# st-link_v2_hall_crossboard_1_1.net
KiCad netlist of a schematic drawn in Altium Designer
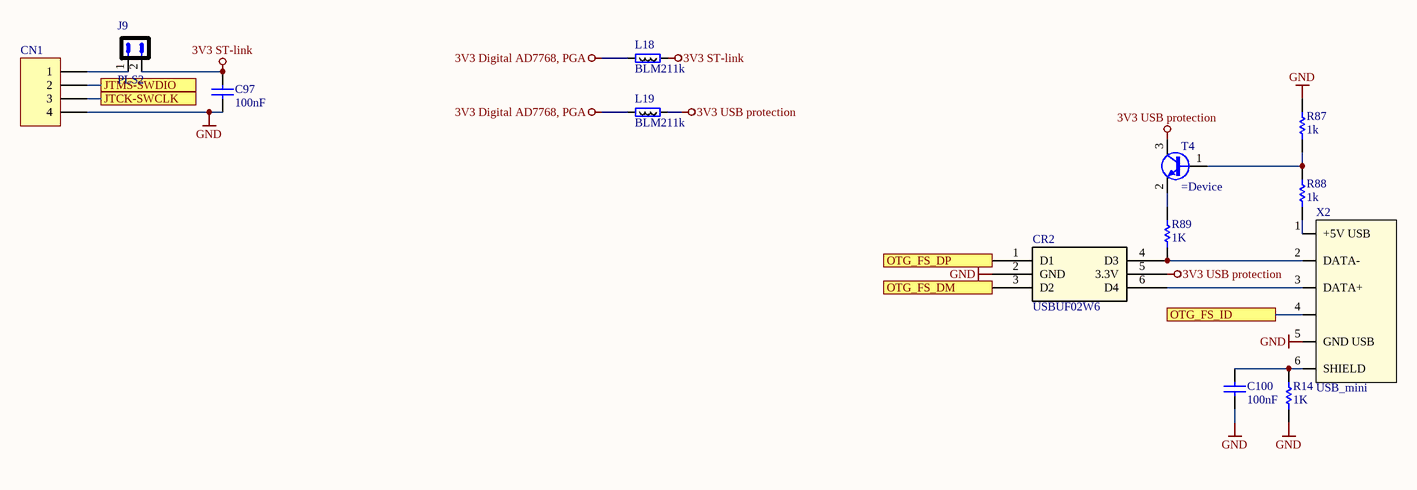
[diagram p0: st-link_v2_hall_crossboard_1_1.SchDoc]

(export (version "E")
  (design (tool "Eeschema 10.0.6"))
  (components
    (comp (ref "C97")
      (value "100nF")
      (footprint "hall_crossboard_1_1_library:0603C")
      (description "Capacitor 0402 / 0603 / 0805")
      (libsource (lib "hall_crossboard_1_1_library") (part "Capacitor_ST"))
    )
    (comp (ref "C100")
      (value "100nF")
      (footprint "hall_crossboard_1_1_library:0603C")
      (description "Capacitor 0402 / 0603 / 0805")
      (libsource (lib "hall_crossboard_1_1_library") (part "Capacitor_ST"))
    )
    (comp (ref "CN1")
      (value "Header 4")
      (footprint "HDR_1x4_2R54_V_M")
      (description "Header, 4-Pin, Single row")
      (fields (field (name "PUBLISHER") "Altium Limited"))
      (libsource (lib "schematic_hall_crossboard_1_1_library") (part "Header 4"))
    )
    (comp (ref "CR2")
      (value "USBUF02W6")
      (footprint "footprint_hall_crossboard_1_1_library:SOTT323-6L_STM-M")
      (description "USB protection")
      (libsource (lib "schematic_hall_crossboard_1_1_library") (part "USBUF02W6"))
    )
    (comp (ref "J9")
      (value "PLS2")
      (footprint "footprint_hall_crossboard_1_1_library:SAMTEC_TSW-102-23-L-S")
      (libsource (lib "schematic_hall_crossboard_1_1_library") (part "PLS2"))
    )
    (comp (ref "L18")
      (value "BLM211k")
      (footprint "footprint_hall_crossboard_1_1_library:RESC2012X50N")
      (description "SMD Ferrite bead 0805")
      (libsource (lib "schematic_hall_crossboard_1_1_library") (part "BLM21"))
    )
    (comp (ref "L19")
      (value "BLM211k")
      (footprint "footprint_hall_crossboard_1_1_library:RESC2012X50N")
      (description "SMD Ferrite bead 0805")
      (libsource (lib "schematic_hall_crossboard_1_1_library") (part "BLM21"))
    )
    (comp (ref "R14")
      (value "1K")
      (footprint "0603R")
      (description "Resistor 0402 / 0603 / 0805")
      (libsource (lib "hall_crossboard_1_1_library") (part "Resistor_ST"))
    )
    (comp (ref "R87")
      (value "1k")
      (footprint "0603R")
      (description "Resistor 0402 / 0603 / 0805")
      (libsource (lib "hall_crossboard_1_1_library") (part "Resistor_ST"))
    )
    (comp (ref "R88")
      (value "1k")
      (footprint "0603R")
      (description "Resistor 0402 / 0603 / 0805")
      (libsource (lib "hall_crossboard_1_1_library") (part "Resistor_ST"))
    )
    (comp (ref "R89")
      (value "1K")
      (footprint "0603R")
      (description "Resistor 0402 / 0603 / 0805")
      (libsource (lib "hall_crossboard_1_1_library") (part "Resistor_ST"))
    )
    (comp (ref "T4")
      (value "~")
      (footprint "SOT-23")
      (description "Bipolar transistor")
      (libsource (lib "hall_crossboard_1_1_library") (part "BC846"))
    )
    (comp (ref "X2")
      (value "USB_mini")
      (footprint "TYCO_1734035-1")
      (description "Вилка  PLS 6x2.54")
      (libsource (lib "hall_crossboard_1_1_library") (part "USB_mini"))
    )
  )
  (nets
    (net (code "1") (name "/JTCK-SWCLK") (class "Default")
      (node (ref "CN1") (pin "3") (pinfunction "3_3") (pintype "passive"))
    )
    (net (code "2") (name "/JTMS-SWDIO") (class "Default")
      (node (ref "CN1") (pin "2") (pinfunction "2_2") (pintype "passive"))
    )
    (net (code "3") (name "/OTG_FS_DM") (class "Default")
      (node (ref "CR2") (pin "3") (pinfunction "D2_3") (pintype "passive"))
    )
    (net (code "4") (name "/OTG_FS_DP") (class "Default")
      (node (ref "CR2") (pin "1") (pinfunction "D1_1") (pintype "passive"))
    )
    (net (code "5") (name "/OTG_FS_ID") (class "Default")
      (node (ref "X2") (pin "4") (pinfunction "4_4") (pintype "passive"))
    )
    (net (code "6") (name "3V3 Digital AD7768, PGA") (class "Default")
      (node (ref "L18") (pin "2") (pinfunction "2_2") (pintype "passive"))
      (node (ref "L19") (pin "2") (pinfunction "2_2") (pintype "passive"))
    )
    (net (code "7") (name "3V3 ST-link") (class "Default")
      (node (ref "C97") (pin "2") (pinfunction "2_2") (pintype "passive"))
      (node (ref "J9") (pin "2") (pinfunction "2_2") (pintype "bidirectional"))
      (node (ref "L18") (pin "1") (pinfunction "1_1") (pintype "passive"))
    )
    (net (code "8") (name "3V3 USB protection") (class "Default")
      (node (ref "CR2") (pin "5") (pinfunction "3.3V_5") (pintype "passive"))
      (node (ref "L19") (pin "1") (pinfunction "1_1") (pintype "passive"))
      (node (ref "T4") (pin "3") (pinfunction "C_3") (pintype "passive"))
    )
    (net (code "9") (name "GND") (class "Default")
      (node (ref "C100") (pin "1") (pinfunction "1_1") (pintype "passive"))
      (node (ref "C97") (pin "1") (pinfunction "1_1") (pintype "passive"))
      (node (ref "CN1") (pin "4") (pinfunction "4_4") (pintype "passive"))
      (node (ref "CR2") (pin "2") (pinfunction "GND_2") (pintype "power_in"))
      (node (ref "R14") (pin "1") (pinfunction "1_1") (pintype "passive"))
      (node (ref "R87") (pin "2") (pinfunction "2_2") (pintype "passive"))
      (node (ref "X2") (pin "5") (pinfunction "GND_USB_5") (pintype "passive"))
    )
    (net (code "10") (name "Net-(CN1-Pad1)") (class "Default")
      (node (ref "CN1") (pin "1") (pinfunction "1_1") (pintype "passive"))
      (node (ref "J9") (pin "1") (pinfunction "1_1") (pintype "bidirectional"))
    )
    (net (code "11") (name "Net-(CR2-D3)") (class "Default")
      (node (ref "CR2") (pin "4") (pinfunction "D3_4") (pintype "passive"))
      (node (ref "R89") (pin "1") (pinfunction "1_1") (pintype "passive"))
      (node (ref "X2") (pin "2") (pinfunction "DATA-_2") (pintype "passive"))
    )
    (net (code "12") (name "Net-(CR2-D4)") (class "Default")
      (node (ref "CR2") (pin "6") (pinfunction "D4_6") (pintype "passive"))
      (node (ref "X2") (pin "3") (pinfunction "DATA+_3") (pintype "passive"))
    )
    (net (code "13") (name "Net-(T4-B)") (class "Default")
      (node (ref "R87") (pin "1") (pinfunction "1_1") (pintype "passive"))
      (node (ref "R88") (pin "2") (pinfunction "2_2") (pintype "passive"))
      (node (ref "T4") (pin "1") (pinfunction "B_1") (pintype "passive"))
    )
    (net (code "14") (name "Net-(T4-E)") (class "Default")
      (node (ref "R89") (pin "2") (pinfunction "2_2") (pintype "passive"))
      (node (ref "T4") (pin "2") (pinfunction "E_2") (pintype "passive"))
    )
    (net (code "15") (name "Net-(X2-+5V_USB)") (class "Default")
      (node (ref "R88") (pin "1") (pinfunction "1_1") (pintype "passive"))
      (node (ref "X2") (pin "1") (pinfunction "+5V_USB_1") (pintype "passive"))
    )
    (net (code "16") (name "Net-(X2-SHIELD)") (class "Default")
      (node (ref "C100") (pin "2") (pinfunction "2_2") (pintype "passive"))
      (node (ref "R14") (pin "2") (pinfunction "2_2") (pintype "passive"))
      (node (ref "X2") (pin "6") (pinfunction "SHIELD_6") (pintype "passive"))
    )
  )
)
